# TM4C-B.net
KiCad netlist of a schematic drawn in Altium Designer
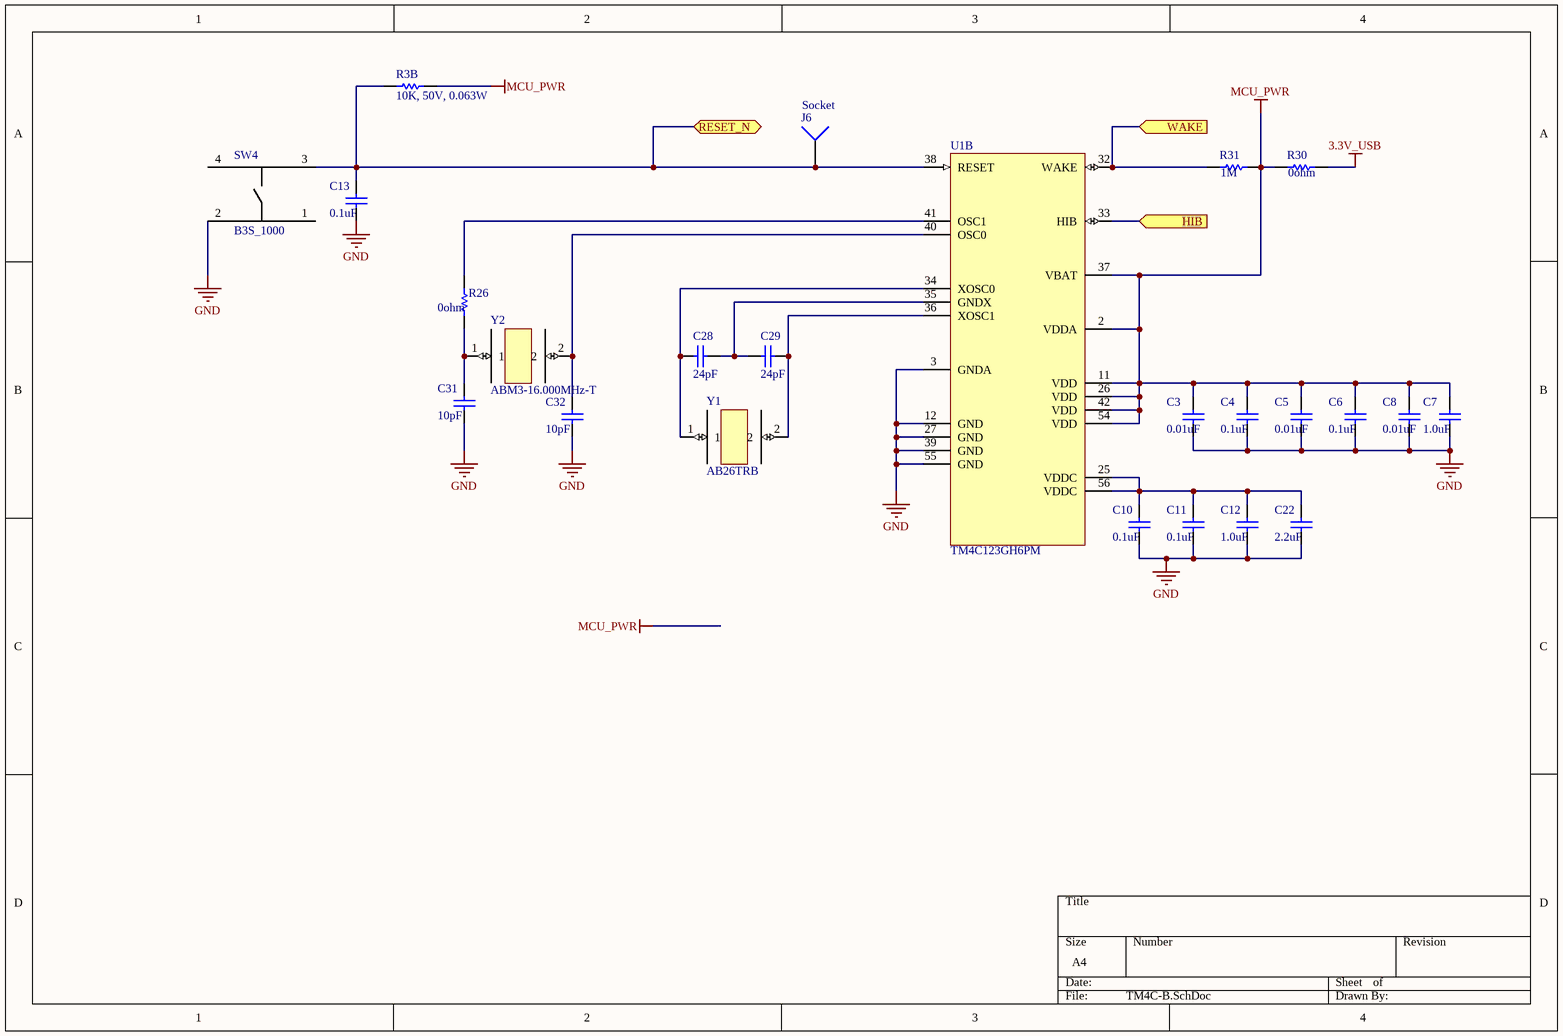
[diagram p0: TM4C-B.SchDoc]

(export (version "E")
  (design (tool "Eeschema 10.0.6"))
  (components
    (comp (ref "C3")
      (value "0.01uF")
      (footprint "C0805")
      (description "Capacitor (Semiconductor SIM Model)")
      (fields (field (name "PUBLISHER") "Altium Limited"))
      (libsource (lib "Miscellaneous Devices") (part "Cap Semi"))
    )
    (comp (ref "C4")
      (value "0.1uF")
      (footprint "C0805")
      (description "Capacitor (Semiconductor SIM Model)")
      (fields (field (name "PUBLISHER") "Altium Limited"))
      (libsource (lib "Miscellaneous Devices") (part "Cap Semi"))
    )
    (comp (ref "C5")
      (value "0.01uF")
      (footprint "C0805")
      (description "Capacitor (Semiconductor SIM Model)")
      (fields (field (name "PUBLISHER") "Altium Limited"))
      (libsource (lib "Miscellaneous Devices") (part "Cap Semi"))
    )
    (comp (ref "C6")
      (value "0.1uF")
      (footprint "C0805")
      (description "Capacitor (Semiconductor SIM Model)")
      (fields (field (name "PUBLISHER") "Altium Limited"))
      (libsource (lib "Miscellaneous Devices") (part "Cap Semi"))
    )
    (comp (ref "C7")
      (value "1.0uF")
      (footprint "C0805")
      (description "Capacitor (Semiconductor SIM Model)")
      (fields (field (name "PUBLISHER") "Altium Limited"))
      (libsource (lib "Miscellaneous Devices") (part "Cap Semi"))
    )
    (comp (ref "C8")
      (value "0.01uF")
      (footprint "C0805")
      (description "Capacitor (Semiconductor SIM Model)")
      (fields (field (name "PUBLISHER") "Altium Limited"))
      (libsource (lib "Miscellaneous Devices") (part "Cap Semi"))
    )
    (comp (ref "C10")
      (value "0.1uF")
      (footprint "C0805")
      (description "Capacitor (Semiconductor SIM Model)")
      (fields (field (name "PUBLISHER") "Altium Limited"))
      (libsource (lib "Miscellaneous Devices") (part "Cap Semi"))
    )
    (comp (ref "C11")
      (value "0.1uF")
      (footprint "C0805")
      (description "Capacitor (Semiconductor SIM Model)")
      (fields (field (name "PUBLISHER") "Altium Limited"))
      (libsource (lib "Miscellaneous Devices") (part "Cap Semi"))
    )
    (comp (ref "C12")
      (value "1.0uF")
      (footprint "C0805")
      (description "Capacitor (Semiconductor SIM Model)")
      (fields (field (name "PUBLISHER") "Altium Limited"))
      (libsource (lib "Miscellaneous Devices") (part "Cap Semi"))
    )
    (comp (ref "C13")
      (value "0.1uF")
      (footprint "C0805")
      (description "Capacitor (Semiconductor SIM Model)")
      (fields (field (name "PUBLISHER") "Altium Limited"))
      (libsource (lib "Miscellaneous Devices") (part "Cap Semi"))
    )
    (comp (ref "C22")
      (value "2.2uF")
      (footprint "C0805")
      (description "Capacitor (Semiconductor SIM Model)")
      (fields (field (name "PUBLISHER") "Altium Limited"))
      (libsource (lib "Miscellaneous Devices") (part "Cap Semi"))
    )
    (comp (ref "C28")
      (value "24pF")
      (footprint "C0805")
      (description "Capacitor (Semiconductor SIM Model)")
      (fields (field (name "PUBLISHER") "Altium Limited"))
      (libsource (lib "Miscellaneous Devices") (part "Cap Semi"))
    )
    (comp (ref "C29")
      (value "24pF")
      (footprint "C0805")
      (description "Capacitor (Semiconductor SIM Model)")
      (fields (field (name "PUBLISHER") "Altium Limited"))
      (libsource (lib "Miscellaneous Devices") (part "Cap Semi"))
    )
    (comp (ref "C31")
      (value "10pF")
      (footprint "C0805")
      (description "Capacitor (Semiconductor SIM Model)")
      (fields (field (name "PUBLISHER") "Altium Limited"))
      (libsource (lib "Miscellaneous Devices") (part "Cap Semi"))
    )
    (comp (ref "C32")
      (value "10pF")
      (footprint "C0805")
      (description "Capacitor (Semiconductor SIM Model)")
      (fields (field (name "PUBLISHER") "Altium Limited"))
      (libsource (lib "Miscellaneous Devices") (part "Cap Semi"))
    )
    (comp (ref "J6")
      (value "Socket")
      (footprint "PIN1")
      (fields (field (name "PUBLISHER") "Altium Limited"))
      (libsource (lib "Miscellaneous Connectors") (part "Socket"))
    )
    (comp (ref "R3B")
      (value "10K, 50V, 0.063W")
      (footprint "ERA-0805")
      (fields (field (name "PUBLISHER") "Altium Limited"))
      (libsource (lib "Panasonic Resistor") (part "ERAS"))
    )
    (comp (ref "R26")
      (value "0ohm")
      (footprint "ERA-0805")
      (fields (field (name "PUBLISHER") "Altium Limited"))
      (libsource (lib "Panasonic Resistor") (part "ERAS"))
    )
    (comp (ref "R30")
      (value "0ohm")
      (footprint "ERA-0805")
      (fields (field (name "PUBLISHER") "Altium Limited"))
      (libsource (lib "Panasonic Resistor") (part "ERAS"))
    )
    (comp (ref "R31")
      (value "1M")
      (footprint "ERA-0805")
      (fields (field (name "PUBLISHER") "Altium Limited"))
      (libsource (lib "Panasonic Resistor") (part "ERAS"))
    )
    (comp (ref "SW4")
      (value "B3S_1000")
      (footprint "TM4C_Launchpad:B3S_1000")
      (libsource (lib "TM4C_Launchpad") (part "B3S_1000"))
    )
    (comp (ref "U1")
      (value "TM4C123GH6PM")
      (footprint "LQFP64_L")
      (libsource (lib "TM4C_Launchpad") (part "TM4C123GH6PM"))
    )
    (comp (ref "Y1")
      (value "AB26TRB")
      (footprint "TM4C_Launchpad:AB26TRB")
      (libsource (lib "TM4C_Launchpad") (part "AB26TRB"))
    )
    (comp (ref "Y2")
      (value "ABM3-16.000MHz-T")
      (footprint "TM4C_Launchpad:ABM3")
      (libsource (lib "TM4C_Launchpad") (part "ABM3"))
    )
  )
  (nets
    (net (code "1") (name "/HIB") (class "Default")
      (node (ref "U1") (pin "33") (pinfunction "HIB_33") (pintype "bidirectional"))
    )
    (net (code "2") (name "/RESET_N") (class "Default")
      (node (ref "C13") (pin "2") (pinfunction "2_2") (pintype "passive"))
      (node (ref "J6") (pin "1") (pinfunction "1_1") (pintype "passive"))
      (node (ref "R3B") (pin "2") (pinfunction "2_2") (pintype "passive"))
      (node (ref "SW4") (pin "3") (pinfunction "3_3") (pintype "passive"))
      (node (ref "U1") (pin "38") (pinfunction "RESET_38") (pintype "input"))
    )
    (net (code "3") (name "/WAKE") (class "Default")
      (node (ref "R31") (pin "2") (pinfunction "2_2") (pintype "passive"))
      (node (ref "U1") (pin "32") (pinfunction "WAKE_32") (pintype "bidirectional"))
    )
    (net (code "4") (name "3.3V_USB") (class "Default")
      (node (ref "R30") (pin "1") (pinfunction "1_1") (pintype "passive"))
    )
    (net (code "5") (name "GND") (class "Default")
      (node (ref "C10") (pin "1") (pinfunction "1_1") (pintype "passive"))
      (node (ref "C11") (pin "1") (pinfunction "1_1") (pintype "passive"))
      (node (ref "C12") (pin "1") (pinfunction "1_1") (pintype "passive"))
      (node (ref "C13") (pin "1") (pinfunction "1_1") (pintype "passive"))
      (node (ref "C22") (pin "1") (pinfunction "1_1") (pintype "passive"))
      (node (ref "C3") (pin "1") (pinfunction "1_1") (pintype "passive"))
      (node (ref "C31") (pin "1") (pinfunction "1_1") (pintype "passive"))
      (node (ref "C32") (pin "1") (pinfunction "1_1") (pintype "passive"))
      (node (ref "C4") (pin "1") (pinfunction "1_1") (pintype "passive"))
      (node (ref "C5") (pin "1") (pinfunction "1_1") (pintype "passive"))
      (node (ref "C6") (pin "1") (pinfunction "1_1") (pintype "passive"))
      (node (ref "C7") (pin "1") (pinfunction "1_1") (pintype "passive"))
      (node (ref "C8") (pin "1") (pinfunction "1_1") (pintype "passive"))
      (node (ref "SW4") (pin "2") (pinfunction "2_2") (pintype "passive"))
      (node (ref "U1") (pin "12") (pinfunction "GND_12") (pintype "power_in"))
      (node (ref "U1") (pin "27") (pinfunction "GND_27") (pintype "power_in"))
      (node (ref "U1") (pin "3") (pinfunction "GNDA_3") (pintype "power_in"))
      (node (ref "U1") (pin "39") (pinfunction "GND_39") (pintype "power_in"))
      (node (ref "U1") (pin "55") (pinfunction "GND_55") (pintype "power_in"))
    )
    (net (code "6") (name "MCU_PWR") (class "Default")
      (node (ref "C3") (pin "2") (pinfunction "2_2") (pintype "passive"))
      (node (ref "C4") (pin "2") (pinfunction "2_2") (pintype "passive"))
      (node (ref "C5") (pin "2") (pinfunction "2_2") (pintype "passive"))
      (node (ref "C6") (pin "2") (pinfunction "2_2") (pintype "passive"))
      (node (ref "C7") (pin "2") (pinfunction "2_2") (pintype "passive"))
      (node (ref "C8") (pin "2") (pinfunction "2_2") (pintype "passive"))
      (node (ref "R30") (pin "2") (pinfunction "2_2") (pintype "passive"))
      (node (ref "R31") (pin "1") (pinfunction "1_1") (pintype "passive"))
      (node (ref "R3B") (pin "1") (pinfunction "1_1") (pintype "passive"))
      (node (ref "U1") (pin "11") (pinfunction "VDD_11") (pintype "power_in"))
      (node (ref "U1") (pin "2") (pinfunction "VDDA_2") (pintype "power_in"))
      (node (ref "U1") (pin "26") (pinfunction "VDD_26") (pintype "power_in"))
      (node (ref "U1") (pin "37") (pinfunction "VBAT_37") (pintype "power_in"))
      (node (ref "U1") (pin "42") (pinfunction "VDD_42") (pintype "power_in"))
      (node (ref "U1") (pin "54") (pinfunction "VDD_54") (pintype "power_in"))
    )
    (net (code "7") (name "Net-(C10-Pad2)") (class "Default")
      (node (ref "C10") (pin "2") (pinfunction "2_2") (pintype "passive"))
      (node (ref "C11") (pin "2") (pinfunction "2_2") (pintype "passive"))
      (node (ref "C12") (pin "2") (pinfunction "2_2") (pintype "passive"))
      (node (ref "C22") (pin "2") (pinfunction "2_2") (pintype "passive"))
      (node (ref "U1") (pin "25") (pinfunction "VDDC_25") (pintype "power_in"))
      (node (ref "U1") (pin "56") (pinfunction "VDDC_56") (pintype "power_in"))
    )
    (net (code "8") (name "Net-(C31-Pad2)") (class "Default")
      (node (ref "C31") (pin "2") (pinfunction "2_2") (pintype "passive"))
      (node (ref "R26") (pin "1") (pinfunction "1_1") (pintype "passive"))
      (node (ref "Y2") (pin "1") (pinfunction "1_1") (pintype "bidirectional"))
    )
    (net (code "9") (name "Net-(U1B-GNDX)") (class "Default")
      (node (ref "C28") (pin "1") (pinfunction "1_1") (pintype "passive"))
      (node (ref "C29") (pin "2") (pinfunction "2_2") (pintype "passive"))
      (node (ref "U1") (pin "35") (pinfunction "GNDX_35") (pintype "power_in"))
    )
    (net (code "10") (name "Net-(U1B-OSC0)") (class "Default")
      (node (ref "C32") (pin "2") (pinfunction "2_2") (pintype "passive"))
      (node (ref "U1") (pin "40") (pinfunction "OSC0_40") (pintype "passive"))
      (node (ref "Y2") (pin "2") (pinfunction "2_2") (pintype "bidirectional"))
    )
    (net (code "11") (name "Net-(U1B-OSC1)") (class "Default")
      (node (ref "R26") (pin "2") (pinfunction "2_2") (pintype "passive"))
      (node (ref "U1") (pin "41") (pinfunction "OSC1_41") (pintype "passive"))
    )
    (net (code "12") (name "Net-(U1B-XOSC0)") (class "Default")
      (node (ref "C28") (pin "2") (pinfunction "2_2") (pintype "passive"))
      (node (ref "U1") (pin "34") (pinfunction "XOSC0_34") (pintype "passive"))
      (node (ref "Y1") (pin "1") (pinfunction "1_1") (pintype "bidirectional"))
    )
    (net (code "13") (name "Net-(U1B-XOSC1)") (class "Default")
      (node (ref "C29") (pin "1") (pinfunction "1_1") (pintype "passive"))
      (node (ref "U1") (pin "36") (pinfunction "XOSC1_36") (pintype "passive"))
      (node (ref "Y1") (pin "2") (pinfunction "2_2") (pintype "bidirectional"))
    )
    (net (code "14") (name "unconnected-(SW4-Pad1)") (class "Default")
      (node (ref "SW4") (pin "1") (pinfunction "1_1") (pintype "passive"))
    )
    (net (code "15") (name "unconnected-(SW4-Pad4)") (class "Default")
      (node (ref "SW4") (pin "4") (pinfunction "4_4") (pintype "passive"))
    )
  )
)
